# mcu.net
KiCad netlist of a schematic drawn in Altium Designer
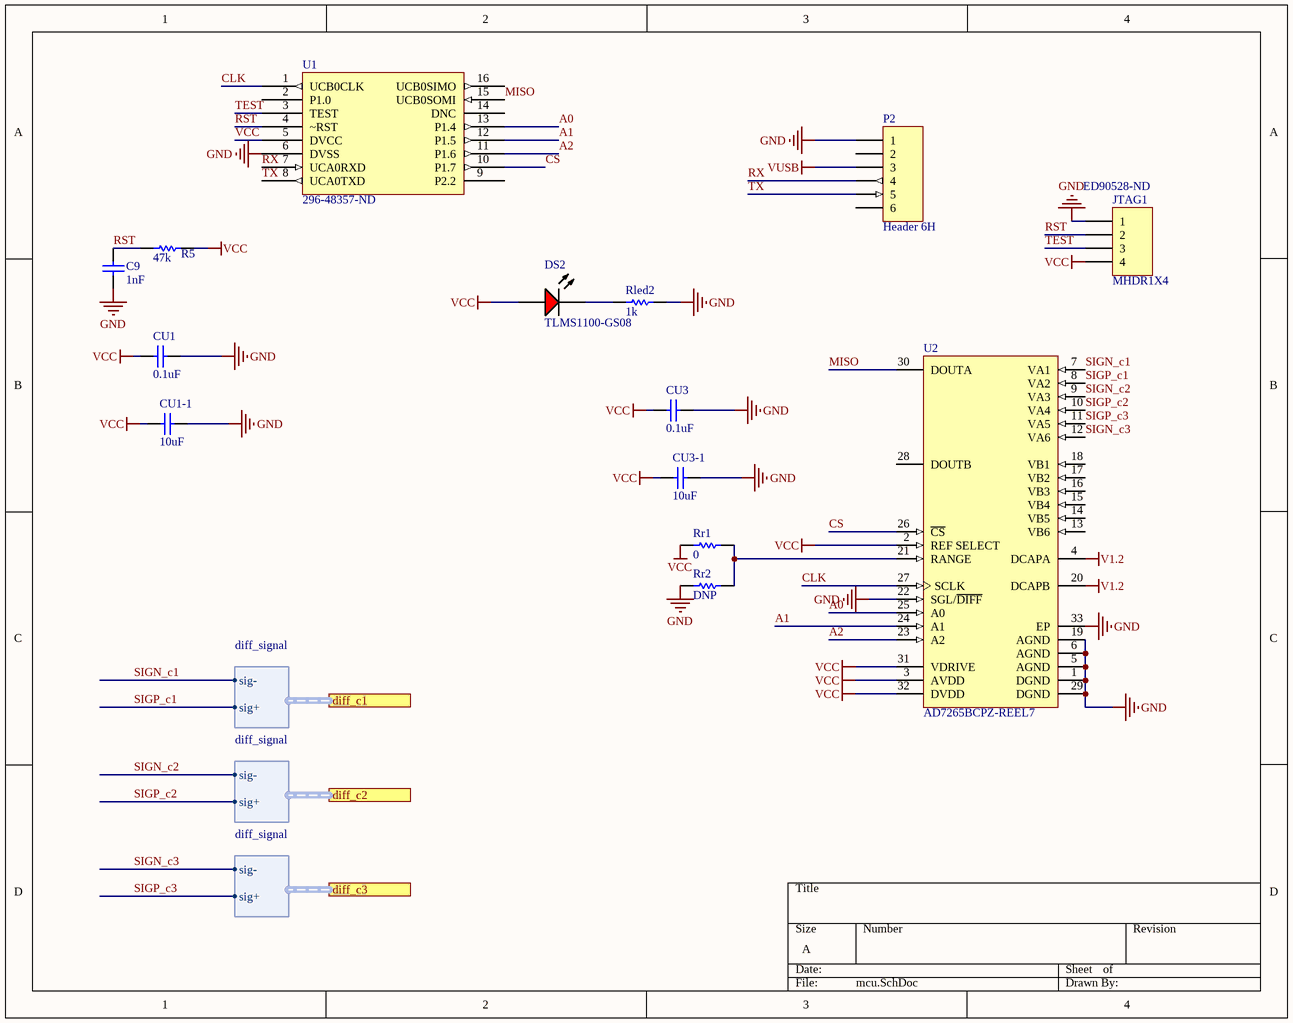
[diagram p0: mcu.SchDoc]

(export (version "E")
  (design (tool "Eeschema 10.0.6"))
  (components
    (comp (ref "C9")
      (value "1nF")
      (footprint "0402")
      (description "Ceramic Capacitor (Surface Mount)")
      (fields (field (name "MANUFACTURER") "Generic Ceramic Chip Cap (TBD)") (field (name "Comment") "Cap"))
      (libsource (lib "maglib") (part "Cap"))
    )
    (comp (ref "CU1")
      (value "0.1uF")
      (footprint "0402")
      (description "Ceramic Capacitor (Surface Mount)")
      (fields (field (name "MANUFACTURER") "Generic Ceramic Chip Cap (TBD)") (field (name "Comment") "Cap"))
      (libsource (lib "maglib") (part "Cap"))
    )
    (comp (ref "CU1-1")
      (value "10uF")
      (footprint "0402")
      (description "Ceramic Capacitor (Surface Mount)")
      (fields (field (name "MANUFACTURER") "Generic Ceramic Chip Cap (TBD)") (field (name "Comment") "Cap"))
      (libsource (lib "maglib") (part "Cap"))
    )
    (comp (ref "CU3")
      (value "0.1uF")
      (footprint "0402")
      (description "Ceramic Capacitor (Surface Mount)")
      (fields (field (name "MANUFACTURER") "Generic Ceramic Chip Cap (TBD)") (field (name "Comment") "Cap"))
      (libsource (lib "maglib") (part "Cap"))
    )
    (comp (ref "CU3-1")
      (value "10uF")
      (footprint "0402")
      (description "Ceramic Capacitor (Surface Mount)")
      (fields (field (name "MANUFACTURER") "Generic Ceramic Chip Cap (TBD)") (field (name "Comment") "Cap"))
      (libsource (lib "maglib") (part "Cap"))
    )
    (comp (ref "DS2")
      (value "TLMS1100-GS08")
      (footprint "VISH-TLMX1100_V")
      (description "LED, RED, 2.1 V, -40 to 100 degC, 2-Pin SMD (0603), RoHS, Tape and Reel")
      (fields (field (name "TOLERANCE") "5%"))
      (libsource (lib "Altium Content Vault") (part "LED-RED-AK-2"))
    )
    (comp (ref "JTAG1")
      (value "MHDR1X4")
      (footprint "MHDR1X4")
      (description "Header, 4-Pin")
      (fields
        (field (name "SUPPLIER PART NUMBER 1") "ED90528-ND")
        (field (name "PUBLISHER") "Altium Limited")
      )
      (libsource (lib "Miscellaneous Connectors") (part "MHDR1X4"))
    )
    (comp (ref "P2")
      (value "Header 6H")
      (footprint "HDR1X6H")
      (description "Header, 6-Pin, Right Angle")
      (fields (field (name "PUBLISHER") "Altium Limited"))
      (libsource (lib "Miscellaneous Connectors") (part "Header 6H"))
    )
    (comp (ref "R5")
      (value "47k")
      (footprint "0402")
      (description "Chip Resistor (Surface Mount)")
      (fields (field (name "MANUFACTURER") "Generic Chip Res (TBD)") (field (name "Comment") "Res"))
      (libsource (lib "maglib") (part "Res"))
    )
    (comp (ref "Rled2")
      (value "1k")
      (footprint "0402")
      (description "Chip Resistor (Surface Mount)")
      (fields (field (name "MANUFACTURER") "Generic Chip Res (TBD)") (field (name "Comment") "Res"))
      (libsource (lib "maglib") (part "Res"))
    )
    (comp (ref "Rr1")
      (value "0")
      (footprint "0402")
      (description "Chip Resistor (Surface Mount)")
      (fields (field (name "MANUFACTURER") "Generic Chip Res (TBD)") (field (name "Comment") "Res"))
      (libsource (lib "maglib") (part "Res"))
    )
    (comp (ref "Rr2")
      (value "DNP")
      (footprint "0402")
      (description "Chip Resistor (Surface Mount)")
      (fields (field (name "MANUFACTURER") "Generic Chip Res (TBD)") (field (name "Comment") "Res"))
      (libsource (lib "maglib") (part "Res"))
    )
    (comp (ref "U1")
      (value "MSP430FR2422")
      (footprint "TSOP65P640X120-16N")
      (description "MSP430FR2422 Mixed-Signal Microcontroller")
      (fields (field (name "SUPPLIER PART NUMBER 1") "296-48357-ND"))
      (libsource (lib "maglib") (part "MSP430FR2422"))
    )
    (comp (ref "U2")
      (value "AD7265BCPZ-REEL7")
      (footprint "CP-32-2_M")
      (fields (field (name "GENERIC PART NUMBER") "AD7265") (field (name "MANUFACTURER") "Analog Devices"))
      (libsource (lib "Altium Content Vault") (part "ADI-AD7265-CP-32-2"))
    )
  )
  (nets
    (net (code "2") (name "/A0") (class "Default")
      (node (ref "U1") (pin "13") (pinfunction "P1.4_13") (pintype "output"))
      (node (ref "U2") (pin "25") (pinfunction "A0_25") (pintype "input"))
    )
    (net (code "3") (name "/A1") (class "Default")
      (node (ref "U1") (pin "12") (pinfunction "P1.5_12") (pintype "output"))
      (node (ref "U2") (pin "24") (pinfunction "A1_24") (pintype "input"))
    )
    (net (code "4") (name "/A2") (class "Default")
      (node (ref "U1") (pin "11") (pinfunction "P1.6_11") (pintype "output"))
      (node (ref "U2") (pin "23") (pinfunction "A2_23") (pintype "input"))
    )
    (net (code "5") (name "/CLK") (class "Default")
      (node (ref "U1") (pin "1") (pinfunction "UCB0CLK_1") (pintype "output"))
      (node (ref "U2") (pin "27") (pinfunction "SCLK_27") (pintype "input"))
    )
    (net (code "6") (name "/CS") (class "Default")
      (node (ref "U1") (pin "10") (pinfunction "P1.7_10") (pintype "output"))
      (node (ref "U2") (pin "26") (pinfunction "~{CS}_26") (pintype "input"))
    )
    (net (code "7") (name "/MISO") (class "Default")
      (node (ref "U1") (pin "15") (pinfunction "UCB0SOMI_15") (pintype "input"))
      (node (ref "U2") (pin "30") (pinfunction "DOUTA_30") (pintype "tri_state"))
    )
    (net (code "8") (name "/RST") (class "Default")
      (node (ref "C9") (pin "2") (pinfunction "2_2") (pintype "passive"))
      (node (ref "JTAG1") (pin "2") (pinfunction "2_2") (pintype "passive"))
      (node (ref "R5") (pin "1") (pinfunction "1_1") (pintype "passive"))
      (node (ref "U1") (pin "4") (pinfunction "~RST_4") (pintype "passive"))
    )
    (net (code "9") (name "/RX") (class "Default")
      (node (ref "P2") (pin "4") (pinfunction "4_4") (pintype "output"))
      (node (ref "U1") (pin "7") (pinfunction "UCA0RXD_7") (pintype "input"))
    )
    (net (code "10") (name "/SIGN_c1") (class "Default")
      (node (ref "U2") (pin "7") (pinfunction "VA1_7") (pintype "input"))
    )
    (net (code "11") (name "/SIGN_c2") (class "Default")
      (node (ref "U2") (pin "9") (pinfunction "VA3_9") (pintype "input"))
    )
    (net (code "12") (name "/SIGN_c3") (class "Default")
      (node (ref "U2") (pin "12") (pinfunction "VA6_12") (pintype "input"))
    )
    (net (code "13") (name "/SIGP_c1") (class "Default")
      (node (ref "U2") (pin "8") (pinfunction "VA2_8") (pintype "input"))
    )
    (net (code "14") (name "/SIGP_c2") (class "Default")
      (node (ref "U2") (pin "10") (pinfunction "VA4_10") (pintype "input"))
    )
    (net (code "15") (name "/SIGP_c3") (class "Default")
      (node (ref "U2") (pin "11") (pinfunction "VA5_11") (pintype "input"))
    )
    (net (code "16") (name "/TEST") (class "Default")
      (node (ref "JTAG1") (pin "3") (pinfunction "3_3") (pintype "passive"))
      (node (ref "U1") (pin "3") (pinfunction "TEST_3") (pintype "passive"))
    )
    (net (code "17") (name "/TX") (class "Default")
      (node (ref "P2") (pin "5") (pinfunction "5_5") (pintype "input"))
      (node (ref "U1") (pin "8") (pinfunction "UCA0TXD_8") (pintype "output"))
    )
    (net (code "19") (name "GND") (class "Default")
      (node (ref "C9") (pin "1") (pinfunction "1_1") (pintype "passive"))
      (node (ref "CU1") (pin "1") (pinfunction "1_1") (pintype "passive"))
      (node (ref "CU1-1") (pin "1") (pinfunction "1_1") (pintype "passive"))
      (node (ref "CU3") (pin "1") (pinfunction "1_1") (pintype "passive"))
      (node (ref "CU3-1") (pin "1") (pinfunction "1_1") (pintype "passive"))
      (node (ref "JTAG1") (pin "1") (pinfunction "1_1") (pintype "passive"))
      (node (ref "P2") (pin "1") (pinfunction "1_1") (pintype "passive"))
      (node (ref "Rled2") (pin "2") (pinfunction "2_2") (pintype "passive"))
      (node (ref "Rr2") (pin "1") (pinfunction "1_1") (pintype "passive"))
      (node (ref "U1") (pin "6") (pinfunction "DVSS_6") (pintype "power_in"))
      (node (ref "U2") (pin "1") (pinfunction "DGND_1") (pintype "power_in"))
      (node (ref "U2") (pin "19") (pinfunction "AGND_19") (pintype "power_in"))
      (node (ref "U2") (pin "22") (pinfunction "SGL/~{DIFF}_22") (pintype "input"))
      (node (ref "U2") (pin "29") (pinfunction "DGND_29") (pintype "power_in"))
      (node (ref "U2") (pin "33") (pinfunction "EP_33") (pintype "power_in"))
      (node (ref "U2") (pin "5") (pinfunction "AGND_5") (pintype "power_in"))
      (node (ref "U2") (pin "6") (pinfunction "AGND_6") (pintype "power_in"))
    )
    (net (code "20") (name "Net-(DS2-K)") (class "Default")
      (node (ref "DS2") (pin "2") (pinfunction "K_2") (pintype "passive"))
      (node (ref "Rled2") (pin "1") (pinfunction "1_1") (pintype "passive"))
    )
    (net (code "21") (name "Net-(U2-RANGE)") (class "Default")
      (node (ref "Rr1") (pin "2") (pinfunction "2_2") (pintype "passive"))
      (node (ref "Rr2") (pin "2") (pinfunction "2_2") (pintype "passive"))
      (node (ref "U2") (pin "21") (pinfunction "RANGE_21") (pintype "input"))
    )
    (net (code "22") (name "V1.2") (class "Default")
      (node (ref "U2") (pin "20") (pinfunction "DCAPB_20") (pintype "passive"))
      (node (ref "U2") (pin "4") (pinfunction "DCAPA_4") (pintype "passive"))
    )
    (net (code "23") (name "VCC") (class "Default")
      (node (ref "CU1") (pin "2") (pinfunction "2_2") (pintype "passive"))
      (node (ref "CU1-1") (pin "2") (pinfunction "2_2") (pintype "passive"))
      (node (ref "CU3") (pin "2") (pinfunction "2_2") (pintype "passive"))
      (node (ref "CU3-1") (pin "2") (pinfunction "2_2") (pintype "passive"))
      (node (ref "DS2") (pin "1") (pinfunction "A_1") (pintype "passive"))
      (node (ref "JTAG1") (pin "4") (pinfunction "4_4") (pintype "passive"))
      (node (ref "R5") (pin "2") (pinfunction "2_2") (pintype "passive"))
      (node (ref "Rr1") (pin "1") (pinfunction "1_1") (pintype "passive"))
      (node (ref "U1") (pin "5") (pinfunction "DVCC_5") (pintype "power_in"))
      (node (ref "U2") (pin "2") (pinfunction "REF_SELECT_2") (pintype "input"))
      (node (ref "U2") (pin "3") (pinfunction "AVDD_3") (pintype "power_in"))
      (node (ref "U2") (pin "31") (pinfunction "VDRIVE_31") (pintype "power_in"))
      (node (ref "U2") (pin "32") (pinfunction "DVDD_32") (pintype "power_in"))
    )
    (net (code "24") (name "VUSB") (class "Default")
      (node (ref "P2") (pin "3") (pinfunction "3_3") (pintype "passive"))
    )
    (net (code "25") (name "unconnected-(P2-Pad2)") (class "Default")
      (node (ref "P2") (pin "2") (pinfunction "2_2") (pintype "passive"))
    )
    (net (code "26") (name "unconnected-(P2-Pad6)") (class "Default")
      (node (ref "P2") (pin "6") (pinfunction "6_6") (pintype "passive"))
    )
    (net (code "27") (name "unconnected-(U1-DNC-Pad14)") (class "Default")
      (node (ref "U1") (pin "14") (pinfunction "DNC_14") (pintype "passive"))
    )
    (net (code "28") (name "unconnected-(U1-P1.0-Pad2)") (class "Default")
      (node (ref "U1") (pin "2") (pinfunction "P1.0_2") (pintype "passive"))
    )
    (net (code "29") (name "unconnected-(U1-P2.2-Pad9)") (class "Default")
      (node (ref "U1") (pin "9") (pinfunction "P2.2_9") (pintype "passive"))
    )
    (net (code "30") (name "unconnected-(U1-UCB0SIMO-Pad16)") (class "Default")
      (node (ref "U1") (pin "16") (pinfunction "UCB0SIMO_16") (pintype "output"))
    )
    (net (code "31") (name "unconnected-(U2-DOUTB-Pad28)") (class "Default")
      (node (ref "U2") (pin "28") (pinfunction "DOUTB_28") (pintype "tri_state"))
    )
    (net (code "32") (name "unconnected-(U2-VB1-Pad18)") (class "Default")
      (node (ref "U2") (pin "18") (pinfunction "VB1_18") (pintype "input"))
    )
    (net (code "33") (name "unconnected-(U2-VB2-Pad17)") (class "Default")
      (node (ref "U2") (pin "17") (pinfunction "VB2_17") (pintype "input"))
    )
    (net (code "34") (name "unconnected-(U2-VB3-Pad16)") (class "Default")
      (node (ref "U2") (pin "16") (pinfunction "VB3_16") (pintype "input"))
    )
    (net (code "35") (name "unconnected-(U2-VB4-Pad15)") (class "Default")
      (node (ref "U2") (pin "15") (pinfunction "VB4_15") (pintype "input"))
    )
    (net (code "36") (name "unconnected-(U2-VB5-Pad14)") (class "Default")
      (node (ref "U2") (pin "14") (pinfunction "VB5_14") (pintype "input"))
    )
    (net (code "37") (name "unconnected-(U2-VB6-Pad13)") (class "Default")
      (node (ref "U2") (pin "13") (pinfunction "VB6_13") (pintype "input"))
    )
  )
)
